# Power_Supply.net
KiCad netlist of a schematic drawn in Altium Designer
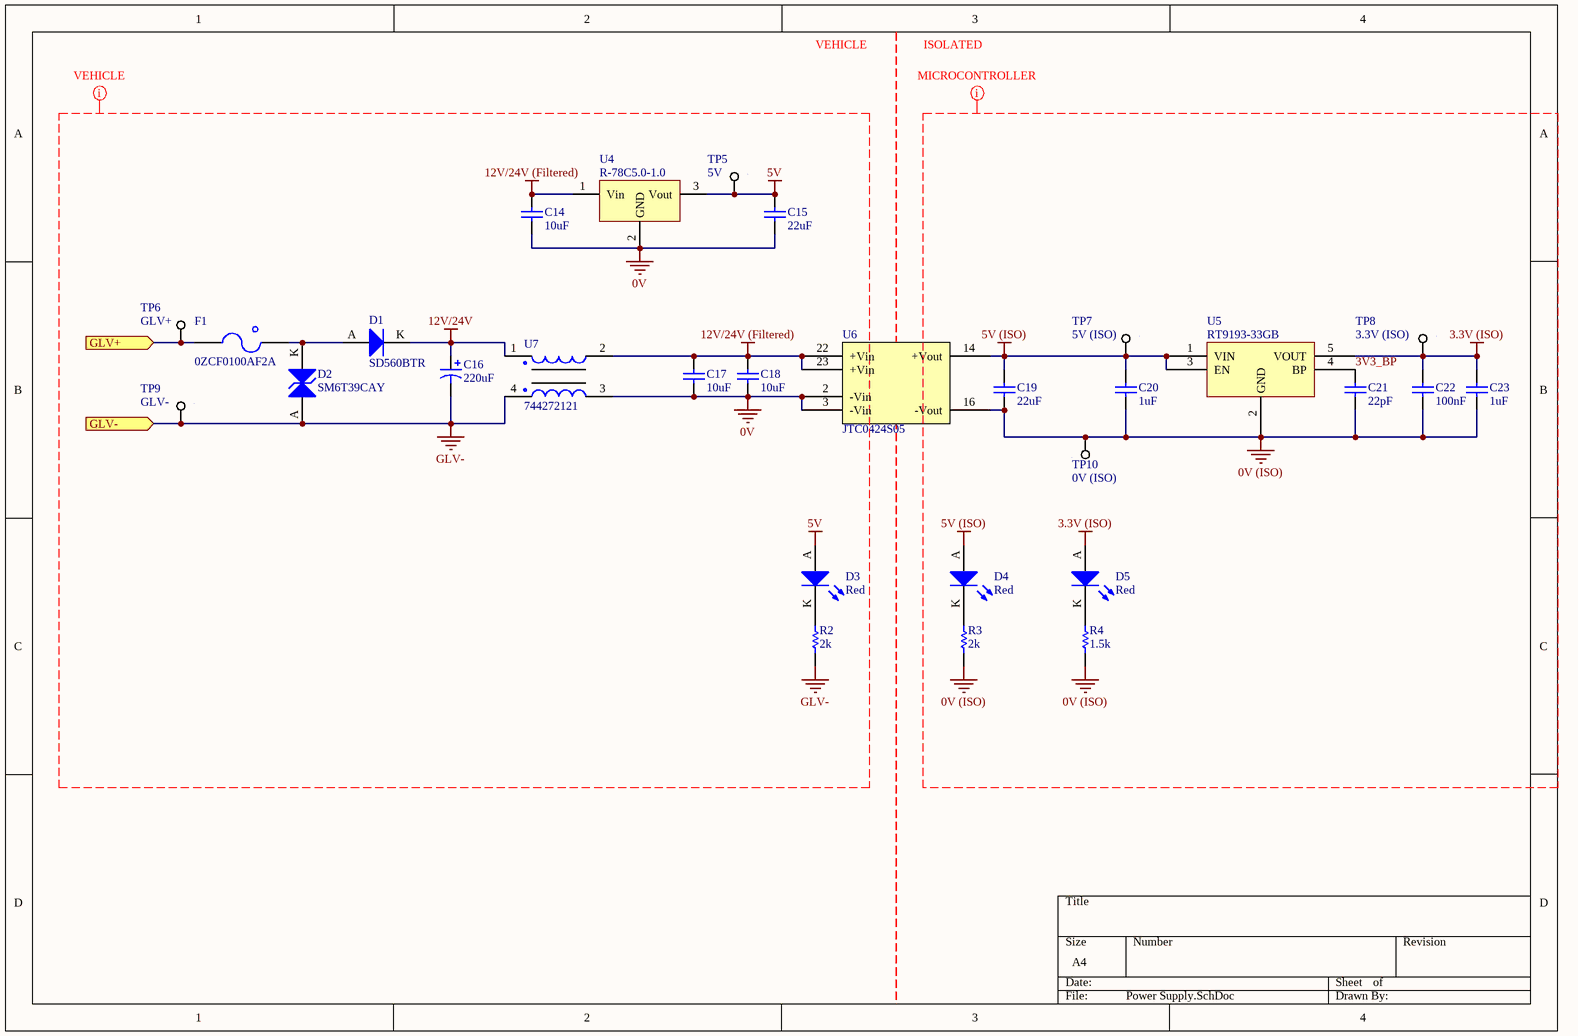
[diagram p0: Power Supply.SchDoc]

(export (version "E")
  (design (tool "Eeschema 10.0.6"))
  (components
    (comp (ref "C14")
      (value "10uF")
      (footprint "0805")
      (fields
        (field (name "PART NUMBER") "GRM21BR6YA106KE43L")
        (field (name "TOLERANCE") "10%")
        (field (name "MANUFACTURER") "muRata")
      )
      (libsource (lib "ts_20-standard-library") (part "Capacitor"))
    )
    (comp (ref "C15")
      (value "22uF")
      (footprint "1206")
      (fields
        (field (name "PART NUMBER") "CC1206MKX5R7BB226")
        (field (name "TOLERANCE") "20%")
        (field (name "MANUFACTURER") "YAGEO")
      )
      (libsource (lib "ts_20-standard-library") (part "Capacitor"))
    )
    (comp (ref "C16")
      (value "~")
      (footprint "Vishay Radial 1213")
      (fields
        (field (name "PART NUMBER") "MAL214699106E3")
        (field (name "TOLERANCE") "20%")
        (field (name "MANUFACTURER") "Vishay")
      )
      (libsource (lib "ts_20-standard-library") (part "Capacitor (Polarised)"))
    )
    (comp (ref "C17")
      (value "10uF")
      (footprint "0805")
      (fields
        (field (name "PART NUMBER") "GRM21BR6YA106KE43L")
        (field (name "TOLERANCE") "10%")
        (field (name "MANUFACTURER") "muRata")
      )
      (libsource (lib "ts_20-standard-library") (part "Capacitor"))
    )
    (comp (ref "C18")
      (value "10uF")
      (footprint "0805")
      (fields
        (field (name "PART NUMBER") "GRM21BR6YA106KE43L")
        (field (name "TOLERANCE") "10%")
        (field (name "MANUFACTURER") "muRata")
      )
      (libsource (lib "ts_20-standard-library") (part "Capacitor"))
    )
    (comp (ref "C19")
      (value "22uF")
      (footprint "1206")
      (fields
        (field (name "PART NUMBER") "CC1206MKX5R7BB226")
        (field (name "TOLERANCE") "20%")
        (field (name "MANUFACTURER") "YAGEO")
      )
      (libsource (lib "ts_20-standard-library") (part "Capacitor"))
    )
    (comp (ref "C20")
      (value "1uF")
      (footprint "0805")
      (fields
        (field (name "PART NUMBER") "AC0805KKX7R8BB105")
        (field (name "TOLERANCE") "10%")
        (field (name "MANUFACTURER") "YAGEO")
      )
      (libsource (lib "ts_20-standard-library") (part "Capacitor"))
    )
    (comp (ref "C21")
      (value "22pF")
      (footprint "0805")
      (fields
        (field (name "PART NUMBER") "GRM21A5C2E220JW01D")
        (field (name "TOLERANCE") "±5%")
        (field (name "MANUFACTURER") "muRata")
      )
      (libsource (lib "ts_20-standard-library") (part "Capacitor"))
    )
    (comp (ref "C22")
      (value "100nF")
      (footprint "0805")
      (fields
        (field (name "PART NUMBER") "GCM21BR71H104KA37L")
        (field (name "TOLERANCE") "±10%")
        (field (name "MANUFACTURER") "muRata")
      )
      (libsource (lib "ts_20-standard-library") (part "Capacitor"))
    )
    (comp (ref "C23")
      (value "1uF")
      (footprint "0805")
      (fields
        (field (name "PART NUMBER") "AC0805KKX7R8BB105")
        (field (name "TOLERANCE") "10%")
        (field (name "MANUFACTURER") "YAGEO")
      )
      (libsource (lib "ts_20-standard-library") (part "Capacitor"))
    )
    (comp (ref "D1")
      (value "SD560BTR")
      (footprint "SMB Diode")
      (description "1.2V_F 600V 5A SMB")
      (fields
        (field (name "MANUFACTURER") "SMC Diode Solutions")
        (field (name "DIGIKEY PART NUMBER") "1655-1530-2-ND")
      )
      (libsource (lib "ts_20-standard-library") (part "Diode"))
    )
    (comp (ref "D2")
      (value "SM6T39CAY")
      (footprint "ST SMB Diode")
      (description "42.8V Clamp 93A (8/20µs) Ipp Tvs Diode Surface Mount SMB (DO-214AA)")
      (fields (field (name "MANUFACTURER") "ST"))
      (libsource (lib "ts_20-standard-library") (part "Bidirectional Zener Diode"))
    )
    (comp (ref "D3")
      (value "Red")
      (footprint "0805 LED")
      (description "Red LED Indication - Discrete 1.75V 0805 (2012 Metric)")
      (fields (field (name "PART NUMBER") "SML-210LTT86") (field (name "MANUFACTURER") "ROHM Semiconductor"))
      (libsource (lib "ts_20-standard-library") (part "LED"))
    )
    (comp (ref "D4")
      (value "Red")
      (footprint "0805 LED")
      (description "Red LED Indication - Discrete 1.75V 0805 (2012 Metric)")
      (fields (field (name "PART NUMBER") "SML-210LTT86") (field (name "MANUFACTURER") "ROHM Semiconductor"))
      (libsource (lib "ts_20-standard-library") (part "LED"))
    )
    (comp (ref "D5")
      (value "Red")
      (footprint "0805 LED")
      (description "Red LED Indication - Discrete 1.75V 0805 (2012 Metric)")
      (fields (field (name "PART NUMBER") "SML-210LTT86") (field (name "MANUFACTURER") "ROHM Semiconductor"))
      (libsource (lib "ts_20-standard-library") (part "LED"))
    )
    (comp (ref "F1")
      (value "0ZCF0100AF2A")
      (footprint "2920")
      (description "PTC RESET FUSE 60V 1A 292")
      (fields
        (field (name "MANUFACTURER") "Littelfuse Inc.")
        (field (name "DIGIKEY PART NUMBER") "507-2070-1-ND")
      )
      (libsource (lib "ts_20-standard-library") (part "PTC Fuse"))
    )
    (comp (ref "R2")
      (value "2k")
      (footprint "0805")
      (fields
        (field (name "PART NUMBER") "RC0805FR072KL")
        (field (name "MANUFACTURER") "YAGEO")
        (field (name "TOLERANCE") "0.01")
      )
      (libsource (lib "ts_20-standard-library") (part "Resistor"))
    )
    (comp (ref "R3")
      (value "2k")
      (footprint "0805")
      (fields
        (field (name "PART NUMBER") "RC0805FR072KL")
        (field (name "MANUFACTURER") "YAGEO")
        (field (name "TOLERANCE") "0.01")
      )
      (libsource (lib "ts_20-standard-library") (part "Resistor"))
    )
    (comp (ref "R4")
      (value "1.5k")
      (footprint "0805")
      (fields
        (field (name "PART NUMBER") "RC0805FR071K5L")
        (field (name "MANUFACTURER") "YAGEO")
        (field (name "TOLERANCE") "0.01")
      )
      (libsource (lib "ts_20-standard-library") (part "Resistor"))
    )
    (comp (ref "TP5")
      (value "5V")
      (footprint "SMD Test Point 1mm")
      (fields (field (name "PART NUMBER") "SMD Test Point Small") (field (name "CONTACT") "NA"))
      (libsource (lib "ts_20-standard-connectors") (part "Test Point Small"))
    )
    (comp (ref "TP6")
      (value "GLV+")
      (footprint "SMD Test Point 1mm")
      (fields (field (name "PART NUMBER") "SMD Test Point Small") (field (name "CONTACT") "NA"))
      (libsource (lib "ts_20-standard-connectors") (part "Test Point Small"))
    )
    (comp (ref "TP7")
      (value "5V (ISO)")
      (footprint "SMD Test Point 1mm")
      (fields (field (name "PART NUMBER") "SMD Test Point Small") (field (name "CONTACT") "NA"))
      (libsource (lib "ts_20-standard-connectors") (part "Test Point Small"))
    )
    (comp (ref "TP8")
      (value "3.3V (ISO)")
      (footprint "SMD Test Point 1mm")
      (fields (field (name "PART NUMBER") "SMD Test Point Small") (field (name "CONTACT") "NA"))
      (libsource (lib "ts_20-standard-connectors") (part "Test Point Small"))
    )
    (comp (ref "TP9")
      (value "GLV-")
      (footprint "SMD Test Point 1mm")
      (fields (field (name "PART NUMBER") "SMD Test Point Small") (field (name "CONTACT") "NA"))
      (libsource (lib "ts_20-standard-connectors") (part "Test Point Small"))
    )
    (comp (ref "TP10")
      (value "0V (ISO)")
      (footprint "SMD Test Point 1mm")
      (fields (field (name "PART NUMBER") "SMD Test Point Small") (field (name "CONTACT") "NA"))
      (libsource (lib "ts_20-standard-connectors") (part "Test Point Small"))
    )
    (comp (ref "U4")
      (value "R-78C5.0-1.0")
      (footprint "RECOM 3-SIP")
      (description "CONV DC/DC 1A 5V OUT SIP VERT")
      (fields (field (name "MANUFACTURER") "Recom") (field (name "DIGIKEY PART NUMBER") "945-1395-5-ND"))
      (libsource (lib "ts_20-standard-library") (part "R-78C5.0-1.0"))
    )
    (comp (ref "U5")
      (value "RT9193-33GB")
      (footprint "RICHTEK SOT-23-5")
      (description "Linear Voltage Regulator IC 1 Output 300mA SOT-23-5")
      (fields (field (name "MANUFACTURER") "Richtek") (field (name "DIGIKEY PART NUMBER") "1028-1014-1-ND"))
      (libsource (lib "ts_20-standard-library") (part "RT9193-33GB"))
    )
    (comp (ref "U6")
      (value "JTC0424S05")
      (footprint "24-DIP Module, 7 Leads")
      (description "DC DC CONVERTER 5V 4W")
      (fields (field (name "MANUFACTURER") "XP Power") (field (name "DIGIKEY PART NUMBER") "JTC0424S05-ND"))
      (libsource (lib "ts_20-standard-library") (part "JTC0424S05"))
    )
    (comp (ref "U7")
      (value "744272121")
      (footprint "Wurth 4-PC Pad")
      (description "120µH @ 100kHz 2 Line Common Mode Choke Surface Mount 460 Ohms @ 30MHz 2.5A DCR 25mOhm")
      (fields
        (field (name "MANUFACTURER") "Wurth Electronics Inc")
        (field (name "DIGIKEY PART NUMBER") "732-1489-1-ND")
      )
      (libsource (lib "ts_20-standard-library") (part "744272121"))
    )
  )
  (nets
    (net (code "1") (name "/3V3_BP") (class "Default")
      (node (ref "C21") (pin "2") (pinfunction "2_2") (pintype "passive"))
      (node (ref "U5") (pin "4") (pinfunction "BP_4") (pintype "passive"))
    )
    (net (code "2") (name "/GLV+") (class "Default")
      (node (ref "F1") (pin "1") (pinfunction "1_1") (pintype "passive"))
      (node (ref "TP6") (pin "1") (pinfunction "1_1") (pintype "passive"))
    )
    (net (code "3") (name "0V") (class "Default")
      (node (ref "C14") (pin "1") (pinfunction "1_1") (pintype "passive"))
      (node (ref "C15") (pin "1") (pinfunction "1_1") (pintype "passive"))
      (node (ref "C17") (pin "1") (pinfunction "1_1") (pintype "passive"))
      (node (ref "C18") (pin "1") (pinfunction "1_1") (pintype "passive"))
      (node (ref "U4") (pin "2") (pinfunction "GND_2") (pintype "passive"))
      (node (ref "U6") (pin "2") (pinfunction "-Vin_2") (pintype "passive"))
      (node (ref "U6") (pin "3") (pinfunction "-Vin_3") (pintype "passive"))
      (node (ref "U7") (pin "3") (pinfunction "3_3") (pintype "power_in"))
    )
    (net (code "4") (name "0V (ISO)") (class "Default")
      (node (ref "C19") (pin "1") (pinfunction "1_1") (pintype "passive"))
      (node (ref "C20") (pin "1") (pinfunction "1_1") (pintype "passive"))
      (node (ref "C21") (pin "1") (pinfunction "1_1") (pintype "passive"))
      (node (ref "C22") (pin "1") (pinfunction "1_1") (pintype "passive"))
      (node (ref "C23") (pin "1") (pinfunction "1_1") (pintype "passive"))
      (node (ref "R3") (pin "1") (pinfunction "1_1") (pintype "passive"))
      (node (ref "R4") (pin "1") (pinfunction "1_1") (pintype "passive"))
      (node (ref "TP10") (pin "1") (pinfunction "1_1") (pintype "passive"))
      (node (ref "U5") (pin "2") (pinfunction "GND_2") (pintype "passive"))
      (node (ref "U6") (pin "16") (pinfunction "-Vout_16") (pintype "passive"))
    )
    (net (code "5") (name "3.3V (ISO)") (class "Default")
      (node (ref "C22") (pin "2") (pinfunction "2_2") (pintype "passive"))
      (node (ref "C23") (pin "2") (pinfunction "2_2") (pintype "passive"))
      (node (ref "D5") (pin "A") (pinfunction "A_A") (pintype "passive"))
      (node (ref "TP8") (pin "1") (pinfunction "1_1") (pintype "passive"))
      (node (ref "U5") (pin "5") (pinfunction "VOUT_5") (pintype "passive"))
    )
    (net (code "6") (name "5V") (class "Default")
      (node (ref "C15") (pin "2") (pinfunction "2_2") (pintype "passive"))
      (node (ref "D3") (pin "A") (pinfunction "A_A") (pintype "passive"))
      (node (ref "TP5") (pin "1") (pinfunction "1_1") (pintype "passive"))
      (node (ref "U4") (pin "3") (pinfunction "Vout_3") (pintype "passive"))
    )
    (net (code "7") (name "5V (ISO)") (class "Default")
      (node (ref "C19") (pin "2") (pinfunction "2_2") (pintype "passive"))
      (node (ref "C20") (pin "2") (pinfunction "2_2") (pintype "passive"))
      (node (ref "D4") (pin "A") (pinfunction "A_A") (pintype "passive"))
      (node (ref "TP7") (pin "1") (pinfunction "1_1") (pintype "passive"))
      (node (ref "U5") (pin "1") (pinfunction "VIN_1") (pintype "passive"))
      (node (ref "U5") (pin "3") (pinfunction "EN_3") (pintype "passive"))
      (node (ref "U6") (pin "14") (pinfunction "+Vout_14") (pintype "passive"))
    )
    (net (code "8") (name "12V{slash}24V") (class "Default")
      (node (ref "C16") (pin "2") (pinfunction "2_2") (pintype "passive"))
      (node (ref "D1") (pin "K") (pinfunction "K_K") (pintype "passive"))
      (node (ref "U7") (pin "1") (pinfunction "1_1") (pintype "passive"))
    )
    (net (code "9") (name "12V{slash}24V (Filtered)") (class "Default")
      (node (ref "C14") (pin "2") (pinfunction "2_2") (pintype "passive"))
      (node (ref "C17") (pin "2") (pinfunction "2_2") (pintype "passive"))
      (node (ref "C18") (pin "2") (pinfunction "2_2") (pintype "passive"))
      (node (ref "U4") (pin "1") (pinfunction "Vin_1") (pintype "passive"))
      (node (ref "U6") (pin "22") (pinfunction "+Vin_22") (pintype "passive"))
      (node (ref "U6") (pin "23") (pinfunction "+Vin_23") (pintype "passive"))
      (node (ref "U7") (pin "2") (pinfunction "2_2") (pintype "passive"))
    )
    (net (code "10") (name "GLV-") (class "Default")
      (node (ref "C16") (pin "1") (pinfunction "1_1") (pintype "passive"))
      (node (ref "D2") (pin "A") (pinfunction "A_A") (pintype "passive"))
      (node (ref "R2") (pin "1") (pinfunction "1_1") (pintype "passive"))
      (node (ref "TP9") (pin "1") (pinfunction "1_1") (pintype "passive"))
      (node (ref "U7") (pin "4") (pinfunction "4_4") (pintype "passive"))
    )
    (net (code "11") (name "Net-(D1-PadA)") (class "Default")
      (node (ref "D1") (pin "A") (pinfunction "A_A") (pintype "passive"))
      (node (ref "D2") (pin "K") (pinfunction "K_K") (pintype "passive"))
      (node (ref "F1") (pin "2") (pinfunction "2_2") (pintype "passive"))
    )
    (net (code "12") (name "Net-(D3-PadK)") (class "Default")
      (node (ref "D3") (pin "K") (pinfunction "K_K") (pintype "passive"))
      (node (ref "R2") (pin "2") (pinfunction "2_2") (pintype "passive"))
    )
    (net (code "13") (name "Net-(D4-PadK)") (class "Default")
      (node (ref "D4") (pin "K") (pinfunction "K_K") (pintype "passive"))
      (node (ref "R3") (pin "2") (pinfunction "2_2") (pintype "passive"))
    )
    (net (code "14") (name "Net-(D5-PadK)") (class "Default")
      (node (ref "D5") (pin "K") (pinfunction "K_K") (pintype "passive"))
      (node (ref "R4") (pin "2") (pinfunction "2_2") (pintype "passive"))
    )
  )
)
